# f103disc_sch.net
KiCad netlist of a schematic drawn in Altium Designer
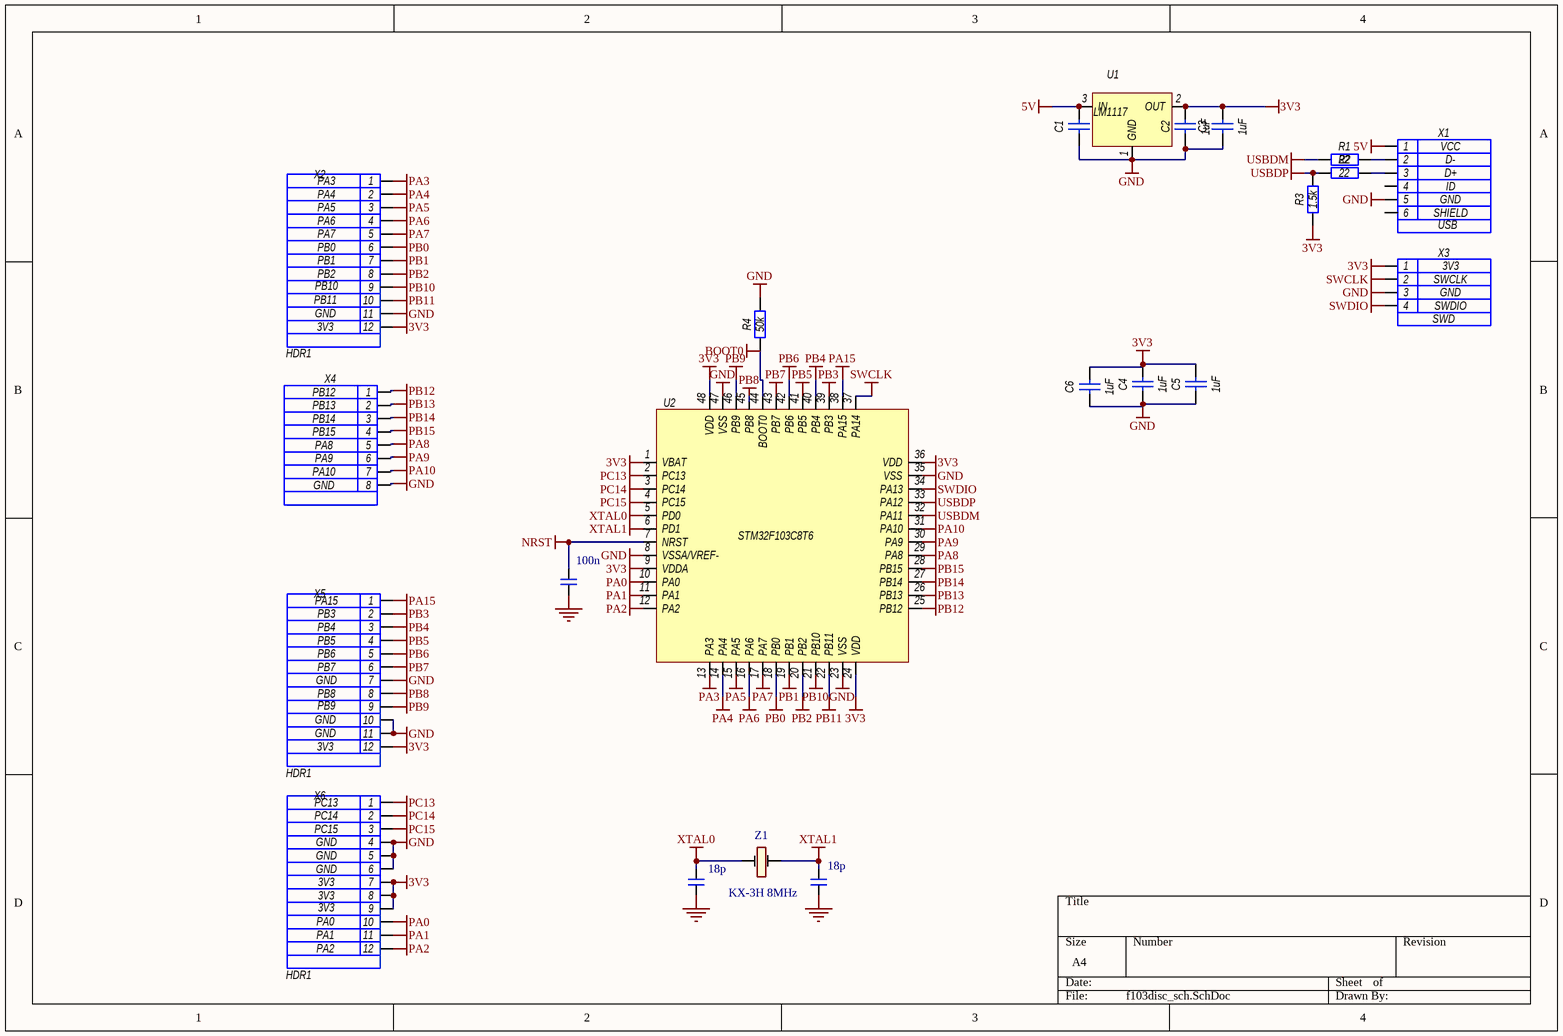
[diagram p0: f103disc_sch.SchDoc]

(export (version "E")
  (design (tool "Eeschema 10.0.6"))
  (components
    (comp (ref "C1")
      (value "1uF")
      (footprint "CAP_0805")
      (description "Конденсатор")
      (libsource (lib "SCH_LIB") (part "Capacitor"))
    )
    (comp (ref "C2")
      (value "1uF")
      (footprint "CAP_0805")
      (description "Конденсатор")
      (libsource (lib "SCH_LIB") (part "Capacitor"))
    )
    (comp (ref "C3")
      (value "1uF")
      (footprint "CAP_0805")
      (description "Конденсатор")
      (libsource (lib "SCH_LIB") (part "Capacitor"))
    )
    (comp (ref "C4")
      (value "1uF")
      (footprint "CAP_0805")
      (description "Конденсатор")
      (libsource (lib "SCH_LIB") (part "Capacitor"))
    )
    (comp (ref "C5")
      (value "1uF")
      (footprint "CAP_0805")
      (description "Конденсатор")
      (libsource (lib "SCH_LIB") (part "Capacitor"))
    )
    (comp (ref "C6")
      (value "1uF")
      (footprint "CAP_0805")
      (description "Конденсатор")
      (libsource (lib "SCH_LIB") (part "Capacitor"))
    )
    (comp (ref "C7")
      (value "CAP0603")
      (footprint "CAP_0603")
      (fields (field (name "BOM") "100n"))
      (libsource (lib "Cap") (part "CAP0603"))
    )
    (comp (ref "C8")
      (value "CAP0603")
      (footprint "CAP_0603")
      (fields (field (name "BOM") "18p"))
      (libsource (lib "Cap") (part "CAP0603"))
    )
    (comp (ref "C9")
      (value "CAP0603")
      (footprint "CAP_0603")
      (fields (field (name "BOM") "18p"))
      (libsource (lib "Cap") (part "CAP0603"))
    )
    (comp (ref "R1")
      (value "22")
      (footprint "RES_0603")
      (description "Резистор")
      (libsource (lib "SCH_LIB") (part "Resisitor"))
    )
    (comp (ref "R2")
      (value "22")
      (footprint "RES_0603")
      (description "Резистор")
      (libsource (lib "SCH_LIB") (part "Resisitor"))
    )
    (comp (ref "R3")
      (value "1.5k")
      (footprint "RES_0603")
      (description "Резистор")
      (libsource (lib "SCH_LIB") (part "Resisitor"))
    )
    (comp (ref "R4")
      (value "50k")
      (footprint "RES_0603")
      (description "Резистор")
      (libsource (lib "SCH_LIB") (part "Resisitor"))
    )
    (comp (ref "U1")
      (value "LM1117")
      (footprint "SOT223")
      (description "Стабилизатор LDO")
      (libsource (lib "SCH_LIB") (part "LM1117"))
    )
    (comp (ref "U2")
      (value "STM32F103C8T6")
      (footprint "PCB_LIB:LQFP48")
      (description "Микроконтроллер")
      (libsource (lib "SCH_LIB") (part "STM32F103C8T6"))
    )
    (comp (ref "X1")
      (value "Model")
      (footprint "USB_MINI-B")
      (description "коннектор USB")
      (fields
        (field (name "NET4") "ID")
        (field (name "NET1") "VCC")
        (field (name "NET2") "D-")
        (field (name "NAME") "USB")
        (field (name "NET3") "D+")
        (field (name "NET5") "GND")
        (field (name "NET6") "SHIELD")
      )
      (libsource (lib "SCH_LIB") (part "miniUSB connector"))
    )
    (comp (ref "X2")
      (value "Model")
      (footprint "PLS-12-3D")
      (fields
        (field (name "NET?") "HDR1")
        (field (name "NET4") "PA6")
        (field (name "NET1") "PA3")
        (field (name "NET2") "PA4")
        (field (name "NET9") "PB10")
        (field (name "NET3") "PA5")
        (field (name "NET5") "PA7")
        (field (name "NET6") "PB0")
        (field (name "NET7") "PB1")
        (field (name "NET8") "PB2")
        (field (name "NET10") "PB11")
        (field (name "NET11") "GND")
        (field (name "NET12") "3V3")
      )
      (libsource (lib "SCH_LIB") (part "Connector 12"))
    )
    (comp (ref "X3")
      (value "SWD")
      (footprint "PLS-4-3D")
      (fields
        (field (name "NET4") "SWDIO")
        (field (name "NET1") "3V3")
        (field (name "NET2") "SWCLK")
        (field (name "NAME") "SWD")
        (field (name "NET3") "GND")
      )
      (libsource (lib "SCH_LIB") (part "Connector 4"))
    )
    (comp (ref "X4")
      (value "Model")
      (footprint "PLS-8-3D")
      (fields
        (field (name "NET4") "PB15")
        (field (name "NET1") "PB12")
        (field (name "NET2") "PB13")
        (field (name "NET3") "PB14")
        (field (name "NET5") "PA8")
        (field (name "NET6") "PA9")
        (field (name "NET7") "PA10")
        (field (name "NET8") "GND")
      )
      (libsource (lib "SCH_LIB") (part "Connector 8"))
    )
    (comp (ref "X5")
      (value "Model")
      (footprint "PLS-12-3D")
      (fields
        (field (name "NET?") "HDR1")
        (field (name "NET4") "PB5")
        (field (name "NET1") "PA15")
        (field (name "NET2") "PB3")
        (field (name "NET9") "PB9")
        (field (name "NET3") "PB4")
        (field (name "NET5") "PB6")
        (field (name "NET6") "PB7")
        (field (name "NET7") "GND")
        (field (name "NET8") "PB8")
        (field (name "NET10") "GND")
        (field (name "NET11") "GND")
        (field (name "NET12") "3V3")
      )
      (libsource (lib "SCH_LIB") (part "Connector 12"))
    )
    (comp (ref "X6")
      (value "Model")
      (footprint "PLS-12-3D")
      (fields
        (field (name "NET?") "HDR1")
        (field (name "NET4") "GND")
        (field (name "NET1") "PC13")
        (field (name "NET2") "PC14")
        (field (name "NET9") "3V3")
        (field (name "NET3") "PC15")
        (field (name "NET5") "GND")
        (field (name "NET6") "GND")
        (field (name "NET7") "3V3")
        (field (name "NET8") "3V3")
        (field (name "NET10") "PA0")
        (field (name "NET11") "PA1")
        (field (name "NET12") "PA2")
      )
      (libsource (lib "SCH_LIB") (part "Connector 12"))
    )
    (comp (ref "Z1")
      (value "HC-49S")
      (footprint "PCB_LIB:HC49S")
      (fields (field (name "BOM") "KX-3H 8MHz"))
      (libsource (lib "Quartz") (part "HC-49S"))
    )
  )
  (nets
    (net (code "1") (name "3V3") (class "Default")
      (node (ref "C2") (pin "2") (pinfunction "2_2") (pintype "passive"))
      (node (ref "C3") (pin "2") (pinfunction "2_2") (pintype "passive"))
      (node (ref "C4") (pin "2") (pinfunction "2_2") (pintype "passive"))
      (node (ref "C5") (pin "2") (pinfunction "2_2") (pintype "passive"))
      (node (ref "C6") (pin "2") (pinfunction "2_2") (pintype "passive"))
      (node (ref "R3") (pin "1") (pinfunction "1_1") (pintype "passive"))
      (node (ref "U1") (pin "2") (pinfunction "OUT_2") (pintype "passive"))
      (node (ref "U2") (pin "1") (pinfunction "VBAT_1") (pintype "passive"))
      (node (ref "U2") (pin "24") (pinfunction "VDD_24") (pintype "passive"))
      (node (ref "U2") (pin "36") (pinfunction "VDD_36") (pintype "passive"))
      (node (ref "U2") (pin "48") (pinfunction "VDD_48") (pintype "passive"))
      (node (ref "U2") (pin "9") (pinfunction "VDDA_9") (pintype "passive"))
      (node (ref "X2") (pin "12") (pinfunction "12_12") (pintype "passive"))
      (node (ref "X3") (pin "1") (pinfunction "1_1") (pintype "passive"))
      (node (ref "X5") (pin "12") (pinfunction "12_12") (pintype "passive"))
      (node (ref "X6") (pin "7") (pinfunction "7_7") (pintype "passive"))
      (node (ref "X6") (pin "8") (pinfunction "8_8") (pintype "passive"))
      (node (ref "X6") (pin "9") (pinfunction "9_9") (pintype "passive"))
    )
    (net (code "2") (name "5V") (class "Default")
      (node (ref "C1") (pin "2") (pinfunction "2_2") (pintype "passive"))
      (node (ref "U1") (pin "3") (pinfunction "IN_3") (pintype "passive"))
      (node (ref "X1") (pin "1") (pinfunction "1_1") (pintype "passive"))
    )
    (net (code "3") (name "BOOT0") (class "Default")
      (node (ref "R4") (pin "1") (pinfunction "1_1") (pintype "passive"))
      (node (ref "U2") (pin "44") (pinfunction "BOOT0_44") (pintype "passive"))
    )
    (net (code "4") (name "GND") (class "Default")
      (node (ref "C1") (pin "1") (pinfunction "1_1") (pintype "passive"))
      (node (ref "C2") (pin "1") (pinfunction "1_1") (pintype "passive"))
      (node (ref "C3") (pin "1") (pinfunction "1_1") (pintype "passive"))
      (node (ref "C4") (pin "1") (pinfunction "1_1") (pintype "passive"))
      (node (ref "C5") (pin "1") (pinfunction "1_1") (pintype "passive"))
      (node (ref "C6") (pin "1") (pinfunction "1_1") (pintype "passive"))
      (node (ref "C7") (pin "2") (pintype "passive"))
      (node (ref "C8") (pin "2") (pintype "passive"))
      (node (ref "C9") (pin "2") (pintype "passive"))
      (node (ref "R4") (pin "2") (pinfunction "2_2") (pintype "passive"))
      (node (ref "U1") (pin "1") (pinfunction "GND_1") (pintype "passive"))
      (node (ref "U2") (pin "23") (pinfunction "VSS_23") (pintype "passive"))
      (node (ref "U2") (pin "35") (pinfunction "VSS_35") (pintype "passive"))
      (node (ref "U2") (pin "47") (pinfunction "VSS_47") (pintype "passive"))
      (node (ref "U2") (pin "8") (pinfunction "VSSA/VREF-_8") (pintype "passive"))
      (node (ref "X1") (pin "5") (pinfunction "5_5") (pintype "passive"))
      (node (ref "X2") (pin "11") (pinfunction "11_11") (pintype "passive"))
      (node (ref "X3") (pin "3") (pinfunction "3_3") (pintype "passive"))
      (node (ref "X4") (pin "8") (pinfunction "8_8") (pintype "passive"))
      (node (ref "X5") (pin "10") (pinfunction "10_10") (pintype "passive"))
      (node (ref "X5") (pin "11") (pinfunction "11_11") (pintype "passive"))
      (node (ref "X5") (pin "7") (pinfunction "7_7") (pintype "passive"))
      (node (ref "X6") (pin "4") (pinfunction "4_4") (pintype "passive"))
      (node (ref "X6") (pin "5") (pinfunction "5_5") (pintype "passive"))
      (node (ref "X6") (pin "6") (pinfunction "6_6") (pintype "passive"))
    )
    (net (code "5") (name "NRST") (class "Default")
      (node (ref "C7") (pin "1") (pintype "passive"))
      (node (ref "U2") (pin "7") (pinfunction "NRST_7") (pintype "passive"))
    )
    (net (code "6") (name "Net-(R1-Pad2)") (class "Default")
      (node (ref "R1") (pin "2") (pinfunction "2_2") (pintype "passive"))
      (node (ref "X1") (pin "2") (pinfunction "2_2") (pintype "passive"))
    )
    (net (code "7") (name "Net-(R2-Pad2)") (class "Default")
      (node (ref "R2") (pin "2") (pinfunction "2_2") (pintype "passive"))
      (node (ref "X1") (pin "3") (pinfunction "3_3") (pintype "passive"))
    )
    (net (code "8") (name "PA0") (class "Default")
      (node (ref "U2") (pin "10") (pinfunction "PA0_10") (pintype "passive"))
      (node (ref "X6") (pin "10") (pinfunction "10_10") (pintype "passive"))
    )
    (net (code "9") (name "PA1") (class "Default")
      (node (ref "U2") (pin "11") (pinfunction "PA1_11") (pintype "passive"))
      (node (ref "X6") (pin "11") (pinfunction "11_11") (pintype "passive"))
    )
    (net (code "10") (name "PA2") (class "Default")
      (node (ref "U2") (pin "12") (pinfunction "PA2_12") (pintype "passive"))
      (node (ref "X6") (pin "12") (pinfunction "12_12") (pintype "passive"))
    )
    (net (code "11") (name "PA3") (class "Default")
      (node (ref "U2") (pin "13") (pinfunction "PA3_13") (pintype "passive"))
      (node (ref "X2") (pin "1") (pinfunction "1_1") (pintype "passive"))
    )
    (net (code "12") (name "PA4") (class "Default")
      (node (ref "U2") (pin "14") (pinfunction "PA4_14") (pintype "passive"))
      (node (ref "X2") (pin "2") (pinfunction "2_2") (pintype "passive"))
    )
    (net (code "13") (name "PA5") (class "Default")
      (node (ref "U2") (pin "15") (pinfunction "PA5_15") (pintype "passive"))
      (node (ref "X2") (pin "3") (pinfunction "3_3") (pintype "passive"))
    )
    (net (code "14") (name "PA6") (class "Default")
      (node (ref "U2") (pin "16") (pinfunction "PA6_16") (pintype "passive"))
      (node (ref "X2") (pin "4") (pinfunction "4_4") (pintype "passive"))
    )
    (net (code "15") (name "PA7") (class "Default")
      (node (ref "U2") (pin "17") (pinfunction "PA7_17") (pintype "passive"))
      (node (ref "X2") (pin "5") (pinfunction "5_5") (pintype "passive"))
    )
    (net (code "16") (name "PA8") (class "Default")
      (node (ref "U2") (pin "29") (pinfunction "PA8_29") (pintype "passive"))
      (node (ref "X4") (pin "5") (pinfunction "5_5") (pintype "passive"))
    )
    (net (code "17") (name "PA9") (class "Default")
      (node (ref "U2") (pin "30") (pinfunction "PA9_30") (pintype "passive"))
      (node (ref "X4") (pin "6") (pinfunction "6_6") (pintype "passive"))
    )
    (net (code "18") (name "PA10") (class "Default")
      (node (ref "U2") (pin "31") (pinfunction "PA10_31") (pintype "passive"))
      (node (ref "X4") (pin "7") (pinfunction "7_7") (pintype "passive"))
    )
    (net (code "19") (name "PA15") (class "Default")
      (node (ref "U2") (pin "38") (pinfunction "PA15_38") (pintype "passive"))
      (node (ref "X5") (pin "1") (pinfunction "1_1") (pintype "passive"))
    )
    (net (code "20") (name "PB0") (class "Default")
      (node (ref "U2") (pin "18") (pinfunction "PB0_18") (pintype "passive"))
      (node (ref "X2") (pin "6") (pinfunction "6_6") (pintype "passive"))
    )
    (net (code "21") (name "PB1") (class "Default")
      (node (ref "U2") (pin "19") (pinfunction "PB1_19") (pintype "passive"))
      (node (ref "X2") (pin "7") (pinfunction "7_7") (pintype "passive"))
    )
    (net (code "22") (name "PB2") (class "Default")
      (node (ref "U2") (pin "20") (pinfunction "PB2_20") (pintype "passive"))
      (node (ref "X2") (pin "8") (pinfunction "8_8") (pintype "passive"))
    )
    (net (code "23") (name "PB3") (class "Default")
      (node (ref "U2") (pin "39") (pinfunction "PB3_39") (pintype "passive"))
      (node (ref "X5") (pin "2") (pinfunction "2_2") (pintype "passive"))
    )
    (net (code "24") (name "PB4") (class "Default")
      (node (ref "U2") (pin "40") (pinfunction "PB4_40") (pintype "passive"))
      (node (ref "X5") (pin "3") (pinfunction "3_3") (pintype "passive"))
    )
    (net (code "25") (name "PB5") (class "Default")
      (node (ref "U2") (pin "41") (pinfunction "PB5_41") (pintype "passive"))
      (node (ref "X5") (pin "4") (pinfunction "4_4") (pintype "passive"))
    )
    (net (code "26") (name "PB6") (class "Default")
      (node (ref "U2") (pin "42") (pinfunction "PB6_42") (pintype "passive"))
      (node (ref "X5") (pin "5") (pinfunction "5_5") (pintype "passive"))
    )
    (net (code "27") (name "PB7") (class "Default")
      (node (ref "U2") (pin "43") (pinfunction "PB7_43") (pintype "passive"))
      (node (ref "X5") (pin "6") (pinfunction "6_6") (pintype "passive"))
    )
    (net (code "28") (name "PB8") (class "Default")
      (node (ref "U2") (pin "45") (pinfunction "PB8_45") (pintype "passive"))
      (node (ref "X5") (pin "8") (pinfunction "8_8") (pintype "passive"))
    )
    (net (code "29") (name "PB9") (class "Default")
      (node (ref "U2") (pin "46") (pinfunction "PB9_46") (pintype "passive"))
      (node (ref "X5") (pin "9") (pinfunction "9_9") (pintype "passive"))
    )
    (net (code "30") (name "PB10") (class "Default")
      (node (ref "U2") (pin "21") (pinfunction "PB10_21") (pintype "passive"))
      (node (ref "X2") (pin "9") (pinfunction "9_9") (pintype "passive"))
    )
    (net (code "31") (name "PB11") (class "Default")
      (node (ref "U2") (pin "22") (pinfunction "PB11_22") (pintype "passive"))
      (node (ref "X2") (pin "10") (pinfunction "10_10") (pintype "passive"))
    )
    (net (code "32") (name "PB12") (class "Default")
      (node (ref "U2") (pin "25") (pinfunction "PB12_25") (pintype "passive"))
      (node (ref "X4") (pin "1") (pinfunction "1_1") (pintype "passive"))
    )
    (net (code "33") (name "PB13") (class "Default")
      (node (ref "U2") (pin "26") (pinfunction "PB13_26") (pintype "passive"))
      (node (ref "X4") (pin "2") (pinfunction "2_2") (pintype "passive"))
    )
    (net (code "34") (name "PB14") (class "Default")
      (node (ref "U2") (pin "27") (pinfunction "PB14_27") (pintype "passive"))
      (node (ref "X4") (pin "3") (pinfunction "3_3") (pintype "passive"))
    )
    (net (code "35") (name "PB15") (class "Default")
      (node (ref "U2") (pin "28") (pinfunction "PB15_28") (pintype "passive"))
      (node (ref "X4") (pin "4") (pinfunction "4_4") (pintype "passive"))
    )
    (net (code "36") (name "PC13") (class "Default")
      (node (ref "U2") (pin "2") (pinfunction "PC13_2") (pintype "passive"))
      (node (ref "X6") (pin "1") (pinfunction "1_1") (pintype "passive"))
    )
    (net (code "37") (name "PC14") (class "Default")
      (node (ref "U2") (pin "3") (pinfunction "PC14_3") (pintype "passive"))
      (node (ref "X6") (pin "2") (pinfunction "2_2") (pintype "passive"))
    )
    (net (code "38") (name "PC15") (class "Default")
      (node (ref "U2") (pin "4") (pinfunction "PC15_4") (pintype "passive"))
      (node (ref "X6") (pin "3") (pinfunction "3_3") (pintype "passive"))
    )
    (net (code "39") (name "SWCLK") (class "Default")
      (node (ref "U2") (pin "37") (pinfunction "PA14_37") (pintype "passive"))
      (node (ref "X3") (pin "2") (pinfunction "2_2") (pintype "passive"))
    )
    (net (code "40") (name "SWDIO") (class "Default")
      (node (ref "U2") (pin "34") (pinfunction "PA13_34") (pintype "passive"))
      (node (ref "X3") (pin "4") (pinfunction "4_4") (pintype "passive"))
    )
    (net (code "41") (name "USBDM") (class "Default")
      (node (ref "R1") (pin "1") (pinfunction "1_1") (pintype "passive"))
      (node (ref "U2") (pin "32") (pinfunction "PA11_32") (pintype "passive"))
    )
    (net (code "42") (name "USBDP") (class "Default")
      (node (ref "R2") (pin "1") (pinfunction "1_1") (pintype "passive"))
      (node (ref "R3") (pin "2") (pinfunction "2_2") (pintype "passive"))
      (node (ref "U2") (pin "33") (pinfunction "PA12_33") (pintype "passive"))
    )
    (net (code "43") (name "XTAL0") (class "Default")
      (node (ref "C8") (pin "1") (pintype "passive"))
      (node (ref "U2") (pin "5") (pinfunction "PD0_5") (pintype "passive"))
      (node (ref "Z1") (pin "1") (pintype "passive"))
    )
    (net (code "44") (name "XTAL1") (class "Default")
      (node (ref "C9") (pin "1") (pintype "passive"))
      (node (ref "U2") (pin "6") (pinfunction "PD1_6") (pintype "passive"))
      (node (ref "Z1") (pin "2") (pintype "passive"))
    )
    (net (code "45") (name "unconnected-(X1-Pad4)") (class "Default")
      (node (ref "X1") (pin "4") (pinfunction "4_4") (pintype "passive"))
    )
    (net (code "46") (name "unconnected-(X1-Pad6)") (class "Default")
      (node (ref "X1") (pin "6") (pinfunction "6_6") (pintype "passive"))
    )
  )
)
